# Sub_Control_Board.net
KiCad netlist of a schematic drawn in EAGLE
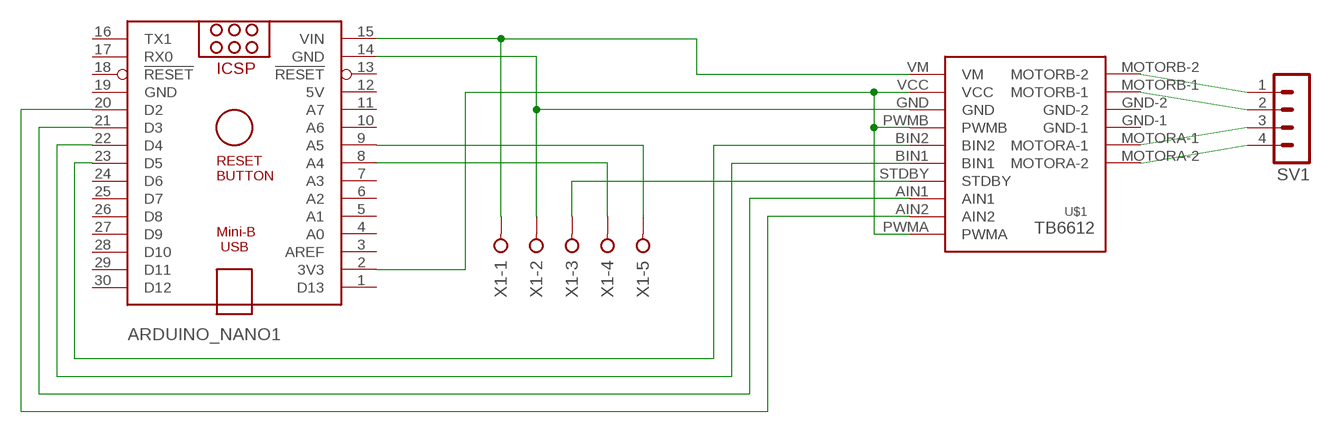
[diagram p0: schematic, sheet 1]

(export (version "E")
  (design (tool "Eeschema 10.0.6"))
  (components
    (comp (ref "ARDUINO_NANO1")
      (value "ARDUINO_NANO")
      (footprint "eagle-import:ARDUINO_NANO")
      (libsource (lib "eagle-import") (part "ARDUINO_NANO"))
    )
    (comp (ref "SV1")
      (value "MA04-1")
      (footprint "eagle-import:MA04-1")
      (libsource (lib "eagle-import") (part "MA04-1"))
    )
    (comp (ref "U$1")
      (value "TB6612-BREAKOUT-MOTOR-CONTROLLER")
      (footprint "eagle-import:TB6612-HEADERS")
      (libsource (lib "eagle-import") (part "TB6612-BREAKOUT-MOTOR-CONTROLLER"))
    )
    (comp (ref "X1")
      (value "W237-05P")
      (footprint "eagle-import:W237-5P")
      (libsource (lib "eagle-import") (part "W237-05P"))
    )
  )
  (nets
    (net (code "1") (name "/5V") (class "Default")
      (node (ref "ARDUINO_NANO1") (pin "12") (pinfunction "5V_12") (pintype "power_in"))
    )
    (net (code "2") (name "/GND") (class "Default")
      (node (ref "ARDUINO_NANO1") (pin "19") (pinfunction "GND_19") (pintype "power_in"))
    )
    (net (code "3") (name "Net-(ARDUINO_NANO1-3V3)") (class "Default")
      (node (ref "ARDUINO_NANO1") (pin "2") (pinfunction "3V3_2") (pintype "output"))
      (node (ref "U$1") (pin "PWMA") (pinfunction "PWMA_PWMA") (pintype "bidirectional"))
      (node (ref "U$1") (pin "PWMB") (pinfunction "PWMB_PWMB") (pintype "bidirectional"))
      (node (ref "U$1") (pin "VCC") (pinfunction "VCC_VCC") (pintype "bidirectional"))
    )
    (net (code "4") (name "Net-(ARDUINO_NANO1-A4)") (class "Default")
      (node (ref "ARDUINO_NANO1") (pin "8") (pinfunction "A4_8") (pintype "bidirectional"))
      (node (ref "X1") (pin "4") (pinfunction "KL_4") (pintype "passive"))
    )
    (net (code "5") (name "Net-(ARDUINO_NANO1-A5)") (class "Default")
      (node (ref "ARDUINO_NANO1") (pin "9") (pinfunction "A5_9") (pintype "bidirectional"))
      (node (ref "X1") (pin "5") (pinfunction "KL_5") (pintype "passive"))
    )
    (net (code "6") (name "Net-(ARDUINO_NANO1-D2)") (class "Default")
      (node (ref "ARDUINO_NANO1") (pin "20") (pinfunction "D2_20") (pintype "bidirectional"))
      (node (ref "U$1") (pin "AIN2") (pinfunction "AIN2_AIN2") (pintype "bidirectional"))
    )
    (net (code "7") (name "Net-(ARDUINO_NANO1-D3)") (class "Default")
      (node (ref "ARDUINO_NANO1") (pin "21") (pinfunction "D3_21") (pintype "bidirectional"))
      (node (ref "U$1") (pin "AIN1") (pinfunction "AIN1_AIN1") (pintype "bidirectional"))
    )
    (net (code "8") (name "Net-(ARDUINO_NANO1-D4)") (class "Default")
      (node (ref "ARDUINO_NANO1") (pin "22") (pinfunction "D4_22") (pintype "bidirectional"))
      (node (ref "U$1") (pin "BIN1") (pinfunction "BIN1_BIN1") (pintype "bidirectional"))
    )
    (net (code "9") (name "Net-(ARDUINO_NANO1-D5)") (class "Default")
      (node (ref "ARDUINO_NANO1") (pin "23") (pinfunction "D5_23") (pintype "bidirectional"))
      (node (ref "U$1") (pin "BIN2") (pinfunction "BIN2_BIN2") (pintype "bidirectional"))
    )
    (net (code "10") (name "Net-(ARDUINO_NANO1-VIN)") (class "Default")
      (node (ref "ARDUINO_NANO1") (pin "15") (pinfunction "VIN_15") (pintype "power_in"))
      (node (ref "U$1") (pin "VM") (pinfunction "VM_VM") (pintype "bidirectional"))
      (node (ref "X1") (pin "1") (pinfunction "KL_1") (pintype "passive"))
    )
    (net (code "11") (name "Net-(SV1-Pad1)") (class "Default")
      (node (ref "SV1") (pin "1") (pinfunction "1_1") (pintype "passive"))
      (node (ref "U$1") (pin "MOTORB-2") (pinfunction "MOTORB-2_MOTORB-2") (pintype "bidirectional"))
    )
    (net (code "12") (name "Net-(SV1-Pad2)") (class "Default")
      (node (ref "SV1") (pin "2") (pinfunction "2_2") (pintype "passive"))
      (node (ref "U$1") (pin "MOTORB-1") (pinfunction "MOTORB-1_MOTORB-1") (pintype "bidirectional"))
    )
    (net (code "13") (name "Net-(SV1-Pad3)") (class "Default")
      (node (ref "SV1") (pin "3") (pinfunction "3_3") (pintype "passive"))
      (node (ref "U$1") (pin "MOTORA-1") (pinfunction "MOTORA-1_MOTORA-1") (pintype "bidirectional"))
    )
    (net (code "14") (name "Net-(SV1-Pad4)") (class "Default")
      (node (ref "SV1") (pin "4") (pinfunction "4_4") (pintype "passive"))
      (node (ref "U$1") (pin "MOTORA-2") (pinfunction "MOTORA-2_MOTORA-2") (pintype "bidirectional"))
    )
    (net (code "15") (name "Net-(X1B-KL)") (class "Default")
      (node (ref "ARDUINO_NANO1") (pin "14") (pinfunction "GND_14") (pintype "power_in"))
      (node (ref "U$1") (pin "GND") (pinfunction "GND_GND") (pintype "bidirectional"))
      (node (ref "X1") (pin "2") (pinfunction "KL_2") (pintype "passive"))
    )
    (net (code "16") (name "Net-(X1C-KL)") (class "Default")
      (node (ref "U$1") (pin "STDBY") (pinfunction "STDBY_STDBY") (pintype "bidirectional"))
      (node (ref "X1") (pin "3") (pinfunction "KL_3") (pintype "passive"))
    )
    (net (code "17") (name "unconnected-(ARDUINO_NANO1-A0-Pad4)") (class "Default")
      (node (ref "ARDUINO_NANO1") (pin "4") (pinfunction "A0_4") (pintype "bidirectional"))
    )
    (net (code "18") (name "unconnected-(ARDUINO_NANO1-A1-Pad5)") (class "Default")
      (node (ref "ARDUINO_NANO1") (pin "5") (pinfunction "A1_5") (pintype "bidirectional"))
    )
    (net (code "19") (name "unconnected-(ARDUINO_NANO1-A2-Pad6)") (class "Default")
      (node (ref "ARDUINO_NANO1") (pin "6") (pinfunction "A2_6") (pintype "bidirectional"))
    )
    (net (code "20") (name "unconnected-(ARDUINO_NANO1-A3-Pad7)") (class "Default")
      (node (ref "ARDUINO_NANO1") (pin "7") (pinfunction "A3_7") (pintype "bidirectional"))
    )
    (net (code "21") (name "unconnected-(ARDUINO_NANO1-A6-Pad10)") (class "Default")
      (node (ref "ARDUINO_NANO1") (pin "10") (pinfunction "A6_10") (pintype "bidirectional"))
    )
    (net (code "22") (name "unconnected-(ARDUINO_NANO1-A7-Pad11)") (class "Default")
      (node (ref "ARDUINO_NANO1") (pin "11") (pinfunction "A7_11") (pintype "bidirectional"))
    )
    (net (code "23") (name "unconnected-(ARDUINO_NANO1-AREF-Pad3)") (class "Default")
      (node (ref "ARDUINO_NANO1") (pin "3") (pinfunction "AREF_3") (pintype "input"))
    )
    (net (code "24") (name "unconnected-(ARDUINO_NANO1-D6-Pad24)") (class "Default")
      (node (ref "ARDUINO_NANO1") (pin "24") (pinfunction "D6_24") (pintype "bidirectional"))
    )
    (net (code "25") (name "unconnected-(ARDUINO_NANO1-D7-Pad25)") (class "Default")
      (node (ref "ARDUINO_NANO1") (pin "25") (pinfunction "D7_25") (pintype "bidirectional"))
    )
    (net (code "26") (name "unconnected-(ARDUINO_NANO1-D8-Pad26)") (class "Default")
      (node (ref "ARDUINO_NANO1") (pin "26") (pinfunction "D8_26") (pintype "bidirectional"))
    )
    (net (code "27") (name "unconnected-(ARDUINO_NANO1-D9-Pad27)") (class "Default")
      (node (ref "ARDUINO_NANO1") (pin "27") (pinfunction "D9_27") (pintype "bidirectional"))
    )
    (net (code "28") (name "unconnected-(ARDUINO_NANO1-D10-Pad28)") (class "Default")
      (node (ref "ARDUINO_NANO1") (pin "28") (pinfunction "D10_28") (pintype "bidirectional"))
    )
    (net (code "29") (name "unconnected-(ARDUINO_NANO1-D11-Pad29)") (class "Default")
      (node (ref "ARDUINO_NANO1") (pin "29") (pinfunction "D11_29") (pintype "bidirectional"))
    )
    (net (code "30") (name "unconnected-(ARDUINO_NANO1-D12-Pad30)") (class "Default")
      (node (ref "ARDUINO_NANO1") (pin "30") (pinfunction "D12_30") (pintype "bidirectional"))
    )
    (net (code "31") (name "unconnected-(ARDUINO_NANO1-D13-Pad1)") (class "Default")
      (node (ref "ARDUINO_NANO1") (pin "1") (pinfunction "D13_1") (pintype "bidirectional"))
    )
    (net (code "32") (name "unconnected-(ARDUINO_NANO1-RX0-Pad17)") (class "Default")
      (node (ref "ARDUINO_NANO1") (pin "17") (pinfunction "RX0_17") (pintype "bidirectional"))
    )
    (net (code "33") (name "unconnected-(ARDUINO_NANO1-TX1-Pad16)") (class "Default")
      (node (ref "ARDUINO_NANO1") (pin "16") (pinfunction "TX1_16") (pintype "bidirectional"))
    )
    (net (code "34") (name "unconnected-(ARDUINO_NANO1-~{RESET}-Pad13)") (class "Default")
      (node (ref "ARDUINO_NANO1") (pin "13") (pinfunction "~{RESET}_13") (pintype "input"))
    )
    (net (code "35") (name "unconnected-(ARDUINO_NANO1-~{RESET}-Pad18)") (class "Default")
      (node (ref "ARDUINO_NANO1") (pin "18") (pinfunction "~{RESET}_18") (pintype "input"))
    )
    (net (code "36") (name "unconnected-(U$1-PadGND-1)") (class "Default")
      (node (ref "U$1") (pin "GND-1") (pinfunction "GND-1_GND-1") (pintype "bidirectional"))
    )
    (net (code "37") (name "unconnected-(U$1-PadGND-2)") (class "Default")
      (node (ref "U$1") (pin "GND-2") (pinfunction "GND-2_GND-2") (pintype "bidirectional"))
    )
  )
)
